# Processing.net
KiCad netlist of a schematic drawn in Altium Designer
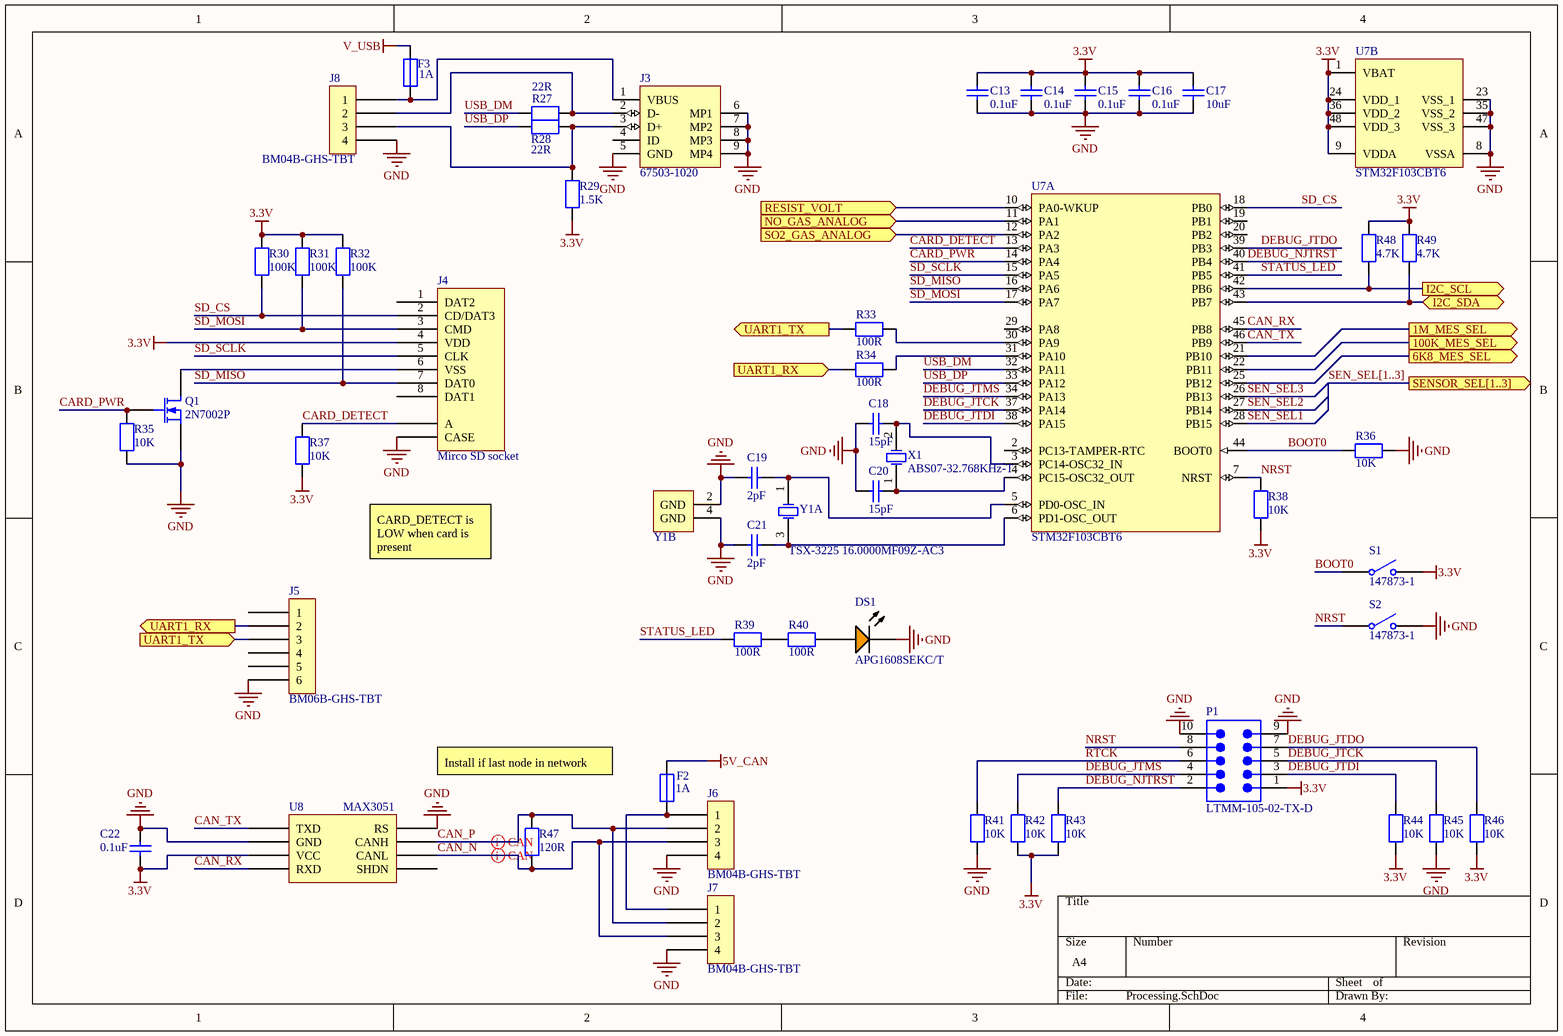
[diagram p0: Processing.SchDoc]

(export (version "E")
  (design (tool "Eeschema 10.0.6"))
  (components
    (comp (ref "C13")
      (value "0.1uF")
      (footprint "0603_CAP")
      (fields (field (name "Comment") "Capacitor"))
      (libsource (lib "Passive_comp") (part "Capacitor"))
    )
    (comp (ref "C14")
      (value "0.1uF")
      (footprint "0603_CAP")
      (fields (field (name "Comment") "Capacitor"))
      (libsource (lib "Passive_comp") (part "Capacitor"))
    )
    (comp (ref "C15")
      (value "0.1uF")
      (footprint "0603_CAP")
      (fields (field (name "Comment") "Capacitor"))
      (libsource (lib "Passive_comp") (part "Capacitor"))
    )
    (comp (ref "C16")
      (value "0.1uF")
      (footprint "0603_CAP")
      (fields (field (name "Comment") "Capacitor"))
      (libsource (lib "Passive_comp") (part "Capacitor"))
    )
    (comp (ref "C17")
      (value "10uF")
      (footprint "1206_CAP")
      (fields (field (name "Comment") "Capacitor"))
      (libsource (lib "Passive_comp") (part "Capacitor"))
    )
    (comp (ref "C18")
      (value "15pF")
      (footprint "0603_CAP")
      (fields (field (name "Comment") "Capacitor"))
      (libsource (lib "Passive_comp") (part "Capacitor"))
    )
    (comp (ref "C19")
      (value "2pF")
      (footprint "0603_CAP")
      (fields (field (name "Comment") "Capacitor"))
      (libsource (lib "Passive_comp") (part "Capacitor"))
    )
    (comp (ref "C20")
      (value "15pF")
      (footprint "0603_CAP")
      (fields (field (name "Comment") "Capacitor"))
      (libsource (lib "Passive_comp") (part "Capacitor"))
    )
    (comp (ref "C21")
      (value "2pF")
      (footprint "0603_CAP")
      (fields (field (name "Comment") "Capacitor"))
      (libsource (lib "Passive_comp") (part "Capacitor"))
    )
    (comp (ref "C22")
      (value "0.1uF")
      (footprint "0603_CAP")
      (fields (field (name "Comment") "Capacitor"))
      (libsource (lib "Passive_comp") (part "Capacitor"))
    )
    (comp (ref "DS1")
      (value "APG1608SEKC/T")
      (footprint "KING-LED0603-25-ORANGE_V")
      (description "LED, SMT, 0603(1608), 0.25mm Tthickness, Super Bright Orange")
      (libsource (lib "Altium Content Vault") (part "KING-LED_ORANGE_A1K2-2"))
    )
    (comp (ref "F2")
      (value "Fuse")
      (footprint "0603_RES")
      (fields (field (name "MAX_A") "1A"))
      (libsource (lib "Passive_comp") (part "Fuse"))
    )
    (comp (ref "F3")
      (value "Fuse")
      (footprint "0603_RES")
      (fields (field (name "MAX_A") "1A"))
      (libsource (lib "Passive_comp") (part "Fuse"))
    )
    (comp (ref "J3")
      (value "67503-1020")
      (footprint "MOLX-67503-1020_V")
      (description "USB, MINI, SMD, RA KME04-USBMU03A01")
      (fields (field (name "MANUFACTURER") "Molex"))
      (libsource (lib "Altium Content Vault") (part "MOLX-67503-1020"))
    )
    (comp (ref "J4")
      (value "Mirco SD socket")
      (footprint "HRS_DM3CS-SF")
      (libsource (lib "Misc_connectors") (part "Micro_SD"))
    )
    (comp (ref "J5")
      (value "BM06B-GHS-TBT")
      (footprint "BM06B-GHS-TBT")
      (description "JST GH top entry SMD connector")
      (libsource (lib "JST-GH") (part "BM06B-GHS-TBT"))
    )
    (comp (ref "J6")
      (value "BM04B-GHS-TBT")
      (footprint "BM04B-GHS-TBT")
      (description "JST GH top entry SMD connector")
      (libsource (lib "") (part "BM04B-GHS-TBT_1"))
    )
    (comp (ref "J7")
      (value "BM04B-GHS-TBT")
      (footprint "BM04B-GHS-TBT")
      (description "JST GH top entry SMD connector")
      (libsource (lib "") (part "BM04B-GHS-TBT_1"))
    )
    (comp (ref "J8")
      (value "BM04B-GHS-TBT")
      (footprint "BM04B-GHS-TBT")
      (description "JST GH top entry SMD connector")
      (libsource (lib "JST-GH") (part "BM04B-GHS-TBT"))
    )
    (comp (ref "P1")
      (value "LTMM-105-02-TX-D")
      (footprint "SMTC-LTMM-105-02-XX-D")
      (description "Shrouded Header & Stacker, Through-Hole, Vertical, -55 to 105 degC, 2 mm Pitch, 10-Pin, Male, RoHS")
      (fields (field (name "MANUFACTURER") "Samtec"))
      (libsource (lib "Altium Content Vault") (part "CMP-1028-00010-1"))
    )
    (comp (ref "Q1")
      (value "N-channel MOSFET")
      (footprint "SOT95P230X110-3M")
      (fields (field (name "PARTNUMBER") "2N7002P"))
      (libsource (lib "Active_comp") (part "MOSFET-N"))
    )
    (comp (ref "R27")
      (value "22R")
      (footprint "0603_RES")
      (fields (field (name "Comment") "Resitor"))
      (libsource (lib "") (part "Resitor_2"))
    )
    (comp (ref "R28")
      (value "22R")
      (footprint "0603_RES")
      (fields (field (name "Comment") "Resitor"))
      (libsource (lib "") (part "Resitor_2"))
    )
    (comp (ref "R29")
      (value "1.5K")
      (footprint "0603_RES")
      (fields (field (name "Comment") "Resitor"))
      (libsource (lib "") (part "Resitor_1"))
    )
    (comp (ref "R30")
      (value "100K")
      (footprint "0603_RES")
      (fields (field (name "Comment") "Resitor"))
      (libsource (lib "") (part "Resitor_1"))
    )
    (comp (ref "R31")
      (value "100K")
      (footprint "0603_RES")
      (fields (field (name "Comment") "Resitor"))
      (libsource (lib "") (part "Resitor_1"))
    )
    (comp (ref "R32")
      (value "100K")
      (footprint "0603_RES")
      (fields (field (name "Comment") "Resitor"))
      (libsource (lib "") (part "Resitor_1"))
    )
    (comp (ref "R33")
      (value "100R")
      (footprint "0603_RES")
      (fields (field (name "Comment") "Resitor"))
      (libsource (lib "") (part "Resitor_2"))
    )
    (comp (ref "R34")
      (value "100R")
      (footprint "0603_RES")
      (fields (field (name "Comment") "Resitor"))
      (libsource (lib "") (part "Resitor_2"))
    )
    (comp (ref "R35")
      (value "10K")
      (footprint "0603_RES")
      (fields (field (name "Comment") "Resitor"))
      (libsource (lib "Passive_comp") (part "Resitor"))
    )
    (comp (ref "R36")
      (value "10K")
      (footprint "0603_RES")
      (fields (field (name "Comment") "Resitor"))
      (libsource (lib "") (part "Resitor_3"))
    )
    (comp (ref "R37")
      (value "10K")
      (footprint "0603_RES")
      (fields (field (name "Comment") "Resitor"))
      (libsource (lib "Passive_comp") (part "Resitor"))
    )
    (comp (ref "R38")
      (value "10K")
      (footprint "0603_RES")
      (fields (field (name "Comment") "Resitor"))
      (libsource (lib "") (part "Resitor_1"))
    )
    (comp (ref "R39")
      (value "100R")
      (footprint "0603_RES")
      (fields (field (name "Comment") "Resitor"))
      (libsource (lib "") (part "Resitor_2"))
    )
    (comp (ref "R40")
      (value "100R")
      (footprint "0603_RES")
      (fields (field (name "Comment") "Resitor"))
      (libsource (lib "") (part "Resitor_2"))
    )
    (comp (ref "R41")
      (value "10K")
      (footprint "0603_RES")
      (fields (field (name "Comment") "Resitor"))
      (libsource (lib "") (part "Resitor_1"))
    )
    (comp (ref "R42")
      (value "10K")
      (footprint "0603_RES")
      (fields (field (name "Comment") "Resitor"))
      (libsource (lib "") (part "Resitor_1"))
    )
    (comp (ref "R43")
      (value "10K")
      (footprint "0603_RES")
      (fields (field (name "Comment") "Resitor"))
      (libsource (lib "Passive_comp") (part "Resitor"))
    )
    (comp (ref "R44")
      (value "10K")
      (footprint "0603_RES")
      (fields (field (name "Comment") "Resitor"))
      (libsource (lib "Passive_comp") (part "Resitor"))
    )
    (comp (ref "R45")
      (value "10K")
      (footprint "0603_RES")
      (fields (field (name "Comment") "Resitor"))
      (libsource (lib "Passive_comp") (part "Resitor"))
    )
    (comp (ref "R46")
      (value "10K")
      (footprint "0603_RES")
      (fields (field (name "Comment") "Resitor"))
      (libsource (lib "") (part "Resitor_1"))
    )
    (comp (ref "R47")
      (value "120R")
      (footprint "0603_RES")
      (fields (field (name "Comment") "Resitor"))
      (libsource (lib "") (part "Resitor_1"))
    )
    (comp (ref "R48")
      (value "4.7K")
      (footprint "0603_RES")
      (fields (field (name "Comment") "Resitor"))
      (libsource (lib "") (part "Resitor_1"))
    )
    (comp (ref "R49")
      (value "4.7K")
      (footprint "0603_RES")
      (fields (field (name "Comment") "Resitor"))
      (libsource (lib "") (part "Resitor_1"))
    )
    (comp (ref "S1")
      (value "147873-1")
      (footprint "147873-1")
      (description "Single-Pole, Single-Throw Switch")
      (fields (field (name "PUBLISHER") "Altium Limited"))
      (libsource (lib "Passive_comp") (part "SW-SPST"))
    )
    (comp (ref "S2")
      (value "147873-1")
      (footprint "147873-1")
      (description "Single-Pole, Single-Throw Switch")
      (fields (field (name "PUBLISHER") "Altium Limited"))
      (libsource (lib "Passive_comp") (part "SW-SPST"))
    )
    (comp (ref "U7")
      (value "STM32F103CBT6")
      (footprint "STM-LQFP48_L")
      (libsource (lib "Altium Content Vault") (part "MC-ARM-STM32F103X8_B-SQ48"))
    )
    (comp (ref "U8")
      (value "MAX3051")
      (footprint "SOIC127P600X175-8M")
      (libsource (lib "Active_comp") (part "MAX3051"))
    )
    (comp (ref "X1")
      (value "ABS07-32.768KHz-T")
      (footprint "ABRA-ABS07-2_V")
      (description "Crystal, 32.768 kHz, 12.5 pF, -40 to 85 degC, SMD Low Profile 3.2 x 1.5 x 0.9 mm, Tape and Reel")
      (fields (field (name "MANUFACTURER") "Abracon"))
      (libsource (lib "Altium Content Vault") (part "ABRA-ABS07-2"))
    )
    (comp (ref "Y1")
      (value "TSX-3225 16.0000MF09Z-AC3")
      (footprint "TSX-3225")
      (libsource (lib "Passive_comp") (part "TSX-3225 16.0000MF09Z-AC3"))
    )
  )
  (nets
    (net (code "1") (name "/1M_MES_SEL") (class "Default")
      (node (ref "U7") (pin "21") (pinfunction "PB10_21") (pintype "bidirectional"))
    )
    (net (code "2") (name "/6K8_MES_SEL") (class "Default")
      (node (ref "U7") (pin "25") (pinfunction "PB12_25") (pintype "bidirectional"))
    )
    (net (code "3") (name "/100K_MES_SEL") (class "Default")
      (node (ref "U7") (pin "22") (pinfunction "PB11_22") (pintype "bidirectional"))
    )
    (net (code "4") (name "/BOOT0") (class "Default")
      (node (ref "R36") (pin "2") (pinfunction "2_2") (pintype "passive"))
      (node (ref "S1") (pin "1") (pinfunction "COMMON_1") (pintype "passive"))
      (node (ref "U7") (pin "44") (pinfunction "BOOT0_44") (pintype "input"))
    )
    (net (code "5") (name "/CAN_N") (class "Default")
      (node (ref "J6") (pin "3") (pinfunction "3_3") (pintype "passive"))
      (node (ref "J7") (pin "3") (pinfunction "3_3") (pintype "passive"))
      (node (ref "R47") (pin "1") (pinfunction "1_1") (pintype "passive"))
      (node (ref "U8") (pin "6") (pinfunction "CANL_6") (pintype "passive"))
    )
    (net (code "6") (name "/CAN_P") (class "Default")
      (node (ref "J6") (pin "2") (pinfunction "2_2") (pintype "passive"))
      (node (ref "J7") (pin "2") (pinfunction "2_2") (pintype "passive"))
      (node (ref "R47") (pin "2") (pinfunction "2_2") (pintype "passive"))
      (node (ref "U8") (pin "7") (pinfunction "CANH_7") (pintype "passive"))
    )
    (net (code "7") (name "/CAN_RX") (class "Default")
      (node (ref "U7") (pin "45") (pinfunction "PB8_45") (pintype "bidirectional"))
      (node (ref "U8") (pin "4") (pinfunction "RXD_4") (pintype "passive"))
    )
    (net (code "8") (name "/CAN_TX") (class "Default")
      (node (ref "U7") (pin "46") (pinfunction "PB9_46") (pintype "bidirectional"))
      (node (ref "U8") (pin "1") (pinfunction "TXD_1") (pintype "passive"))
    )
    (net (code "9") (name "/CARD_DETECT") (class "Default")
      (node (ref "J4") (pin "A") (pinfunction "A_A") (pintype "passive"))
      (node (ref "R37") (pin "1") (pinfunction "1_1") (pintype "passive"))
      (node (ref "U7") (pin "13") (pinfunction "PA3_13") (pintype "bidirectional"))
    )
    (net (code "10") (name "/CARD_PWR") (class "Default")
      (node (ref "Q1") (pin "2") (pinfunction "G_2") (pintype "passive"))
      (node (ref "R35") (pin "1") (pinfunction "1_1") (pintype "passive"))
      (node (ref "U7") (pin "14") (pinfunction "PA4_14") (pintype "bidirectional"))
    )
    (net (code "11") (name "/DEBUG_JTCK") (class "Default")
      (node (ref "P1") (pin "5") (pinfunction "5_5") (pintype "passive"))
      (node (ref "R45") (pin "1") (pinfunction "1_1") (pintype "passive"))
      (node (ref "U7") (pin "37") (pinfunction "PA14_37") (pintype "bidirectional"))
    )
    (net (code "12") (name "/DEBUG_JTDI") (class "Default")
      (node (ref "P1") (pin "3") (pinfunction "3_3") (pintype "passive"))
      (node (ref "R44") (pin "1") (pinfunction "1_1") (pintype "passive"))
      (node (ref "U7") (pin "38") (pinfunction "PA15_38") (pintype "bidirectional"))
    )
    (net (code "13") (name "/DEBUG_JTDO") (class "Default")
      (node (ref "P1") (pin "7") (pinfunction "7_7") (pintype "passive"))
      (node (ref "R46") (pin "2") (pinfunction "2_2") (pintype "passive"))
      (node (ref "U7") (pin "39") (pinfunction "PB3_39") (pintype "bidirectional"))
    )
    (net (code "14") (name "/DEBUG_JTMS") (class "Default")
      (node (ref "P1") (pin "4") (pinfunction "4_4") (pintype "passive"))
      (node (ref "R42") (pin "2") (pinfunction "2_2") (pintype "passive"))
      (node (ref "U7") (pin "34") (pinfunction "PA13_34") (pintype "bidirectional"))
    )
    (net (code "15") (name "/DEBUG_NJTRST") (class "Default")
      (node (ref "P1") (pin "2") (pinfunction "2_2") (pintype "passive"))
      (node (ref "R43") (pin "1") (pinfunction "1_1") (pintype "passive"))
      (node (ref "U7") (pin "40") (pinfunction "PB4_40") (pintype "bidirectional"))
    )
    (net (code "16") (name "/I2C_SCL") (class "Default")
      (node (ref "R48") (pin "1") (pinfunction "1_1") (pintype "passive"))
      (node (ref "U7") (pin "42") (pinfunction "PB6_42") (pintype "bidirectional"))
    )
    (net (code "17") (name "/I2C_SDA") (class "Default")
      (node (ref "R49") (pin "1") (pinfunction "1_1") (pintype "passive"))
      (node (ref "U7") (pin "43") (pinfunction "PB7_43") (pintype "bidirectional"))
    )
    (net (code "18") (name "/NO_GAS_ANALOG") (class "Default")
      (node (ref "U7") (pin "11") (pinfunction "PA1_11") (pintype "bidirectional"))
    )
    (net (code "19") (name "/NRST") (class "Default")
      (node (ref "P1") (pin "8") (pinfunction "8_8") (pintype "passive"))
      (node (ref "R38") (pin "2") (pinfunction "2_2") (pintype "passive"))
      (node (ref "S2") (pin "1") (pinfunction "COMMON_1") (pintype "passive"))
      (node (ref "U7") (pin "7") (pinfunction "NRST_7") (pintype "bidirectional"))
    )
    (net (code "20") (name "/RESIST_VOLT") (class "Default")
      (node (ref "U7") (pin "10") (pinfunction "PA0-WKUP_10") (pintype "bidirectional"))
    )
    (net (code "21") (name "/RTCK") (class "Default")
      (node (ref "P1") (pin "6") (pinfunction "6_6") (pintype "passive"))
      (node (ref "R41") (pin "2") (pinfunction "2_2") (pintype "passive"))
    )
    (net (code "22") (name "/SD_CS") (class "Default")
      (node (ref "J4") (pin "2") (pinfunction "CD/DAT3_2") (pintype "passive"))
      (node (ref "R30") (pin "1") (pinfunction "1_1") (pintype "passive"))
      (node (ref "U7") (pin "18") (pinfunction "PB0_18") (pintype "bidirectional"))
    )
    (net (code "23") (name "/SD_MISO") (class "Default")
      (node (ref "J4") (pin "7") (pinfunction "DAT0_7") (pintype "passive"))
      (node (ref "R32") (pin "1") (pinfunction "1_1") (pintype "passive"))
      (node (ref "U7") (pin "16") (pinfunction "PA6_16") (pintype "bidirectional"))
    )
    (net (code "24") (name "/SD_MOSI") (class "Default")
      (node (ref "J4") (pin "3") (pinfunction "CMD_3") (pintype "passive"))
      (node (ref "R31") (pin "1") (pinfunction "1_1") (pintype "passive"))
      (node (ref "U7") (pin "17") (pinfunction "PA7_17") (pintype "bidirectional"))
    )
    (net (code "25") (name "/SD_SCLK") (class "Default")
      (node (ref "J4") (pin "5") (pinfunction "CLK_5") (pintype "passive"))
      (node (ref "U7") (pin "15") (pinfunction "PA5_15") (pintype "bidirectional"))
    )
    (net (code "26") (name "/SEN_SEL1") (class "Default")
      (node (ref "U7") (pin "28") (pinfunction "PB15_28") (pintype "bidirectional"))
    )
    (net (code "27") (name "/SEN_SEL2") (class "Default")
      (node (ref "U7") (pin "27") (pinfunction "PB14_27") (pintype "bidirectional"))
    )
    (net (code "28") (name "/SEN_SEL3") (class "Default")
      (node (ref "U7") (pin "26") (pinfunction "PB13_26") (pintype "bidirectional"))
    )
    (net (code "30") (name "/SO2_GAS_ANALOG") (class "Default")
      (node (ref "U7") (pin "12") (pinfunction "PA2_12") (pintype "bidirectional"))
    )
    (net (code "31") (name "/STATUS_LED") (class "Default")
      (node (ref "R39") (pin "1") (pinfunction "1_1") (pintype "passive"))
      (node (ref "U7") (pin "41") (pinfunction "PB5_41") (pintype "bidirectional"))
    )
    (net (code "32") (name "/UART1_RX") (class "Default")
      (node (ref "J5") (pin "2") (pinfunction "2_2") (pintype "passive"))
      (node (ref "R34") (pin "1") (pinfunction "1_1") (pintype "passive"))
    )
    (net (code "33") (name "/UART1_TX") (class "Default")
      (node (ref "J5") (pin "3") (pinfunction "3_3") (pintype "passive"))
      (node (ref "R33") (pin "1") (pinfunction "1_1") (pintype "passive"))
    )
    (net (code "34") (name "/USB_DM") (class "Default")
      (node (ref "R27") (pin "1") (pinfunction "1_1") (pintype "passive"))
      (node (ref "U7") (pin "32") (pinfunction "PA11_32") (pintype "bidirectional"))
    )
    (net (code "35") (name "/USB_DP") (class "Default")
      (node (ref "R28") (pin "1") (pinfunction "1_1") (pintype "passive"))
      (node (ref "U7") (pin "33") (pinfunction "PA12_33") (pintype "bidirectional"))
    )
    (net (code "36") (name "3.3V") (class "Default")
      (node (ref "C13") (pin "2") (pinfunction "2_2") (pintype "passive"))
      (node (ref "C14") (pin "2") (pinfunction "2_2") (pintype "passive"))
      (node (ref "C15") (pin "2") (pinfunction "2_2") (pintype "passive"))
      (node (ref "C16") (pin "2") (pinfunction "2_2") (pintype "passive"))
      (node (ref "C17") (pin "2") (pinfunction "2_2") (pintype "passive"))
      (node (ref "C22") (pin "1") (pinfunction "1_1") (pintype "passive"))
      (node (ref "J4") (pin "4") (pinfunction "VDD_4") (pintype "passive"))
      (node (ref "P1") (pin "1") (pinfunction "1_1") (pintype "passive"))
      (node (ref "R29") (pin "1") (pinfunction "1_1") (pintype "passive"))
      (node (ref "R30") (pin "2") (pinfunction "2_2") (pintype "passive"))
      (node (ref "R31") (pin "2") (pinfunction "2_2") (pintype "passive"))
      (node (ref "R32") (pin "2") (pinfunction "2_2") (pintype "passive"))
      (node (ref "R37") (pin "2") (pinfunction "2_2") (pintype "passive"))
      (node (ref "R38") (pin "1") (pinfunction "1_1") (pintype "passive"))
      (node (ref "R42") (pin "1") (pinfunction "1_1") (pintype "passive"))
      (node (ref "R43") (pin "2") (pinfunction "2_2") (pintype "passive"))
      (node (ref "R44") (pin "2") (pinfunction "2_2") (pintype "passive"))
      (node (ref "R46") (pin "1") (pinfunction "1_1") (pintype "passive"))
      (node (ref "R48") (pin "2") (pinfunction "2_2") (pintype "passive"))
      (node (ref "R49") (pin "2") (pinfunction "2_2") (pintype "passive"))
      (node (ref "S1") (pin "2") (pinfunction "NO_2") (pintype "passive"))
      (node (ref "U7") (pin "1") (pinfunction "VBAT_1") (pintype "power_in"))
      (node (ref "U7") (pin "24") (pinfunction "VDD_1_24") (pintype "power_in"))
      (node (ref "U7") (pin "36") (pinfunction "VDD_2_36") (pintype "power_in"))
      (node (ref "U7") (pin "48") (pinfunction "VDD_3_48") (pintype "power_in"))
      (node (ref "U7") (pin "9") (pinfunction "VDDA_9") (pintype "power_in"))
      (node (ref "U8") (pin "3") (pinfunction "VCC_3") (pintype "passive"))
    )
    (net (code "37") (name "5V_CAN") (class "Default")
      (node (ref "F2") (pin "2") (pinfunction "2_2") (pintype "passive"))
    )
    (net (code "38") (name "GND") (class "Default")
      (node (ref "C13") (pin "1") (pinfunction "1_1") (pintype "passive"))
      (node (ref "C14") (pin "1") (pinfunction "1_1") (pintype "passive"))
      (node (ref "C15") (pin "1") (pinfunction "1_1") (pintype "passive"))
      (node (ref "C16") (pin "1") (pinfunction "1_1") (pintype "passive"))
      (node (ref "C17") (pin "1") (pinfunction "1_1") (pintype "passive"))
      (node (ref "C18") (pin "1") (pinfunction "1_1") (pintype "passive"))
      (node (ref "C19") (pin "1") (pinfunction "1_1") (pintype "passive"))
      (node (ref "C20") (pin "1") (pinfunction "1_1") (pintype "passive"))
      (node (ref "C21") (pin "1") (pinfunction "1_1") (pintype "passive"))
      (node (ref "C22") (pin "2") (pinfunction "2_2") (pintype "passive"))
      (node (ref "DS1") (pin "2") (pinfunction "K_2") (pintype "passive"))
      (node (ref "J3") (pin "5") (pinfunction "GND_5") (pintype "power_in"))
      (node (ref "J3") (pin "6") (pinfunction "MP1_6") (pintype "passive"))
      (node (ref "J3") (pin "7") (pinfunction "MP2_7") (pintype "passive"))
      (node (ref "J3") (pin "8") (pinfunction "MP3_8") (pintype "passive"))
      (node (ref "J3") (pin "9") (pinfunction "MP4_9") (pintype "passive"))
      (node (ref "J4") (pin "0") (pinfunction "CASE_0") (pintype "passive"))
      (node (ref "J5") (pin "6") (pinfunction "6_6") (pintype "passive"))
      (node (ref "J6") (pin "4") (pinfunction "4_4") (pintype "passive"))
      (node (ref "J7") (pin "4") (pinfunction "4_4") (pintype "passive"))
      (node (ref "J8") (pin "4") (pinfunction "4_4") (pintype "passive"))
      (node (ref "P1") (pin "10") (pinfunction "10_10") (pintype "passive"))
      (node (ref "P1") (pin "9") (pinfunction "9_9") (pintype "passive"))
      (node (ref "Q1") (pin "3") (pinfunction "S_3") (pintype "passive"))
      (node (ref "R35") (pin "2") (pinfunction "2_2") (pintype "passive"))
      (node (ref "R36") (pin "1") (pinfunction "1_1") (pintype "passive"))
      (node (ref "R41") (pin "1") (pinfunction "1_1") (pintype "passive"))
      (node (ref "R45") (pin "2") (pinfunction "2_2") (pintype "passive"))
      (node (ref "S2") (pin "2") (pinfunction "NO_2") (pintype "passive"))
      (node (ref "U7") (pin "23") (pinfunction "VSS_1_23") (pintype "power_in"))
      (node (ref "U7") (pin "35") (pinfunction "VSS_2_35") (pintype "power_in"))
      (node (ref "U7") (pin "47") (pinfunction "VSS_3_47") (pintype "power_in"))
      (node (ref "U7") (pin "8") (pinfunction "VSSA_8") (pintype "power_in"))
      (node (ref "U8") (pin "2") (pinfunction "GND_2") (pintype "passive"))
      (node (ref "U8") (pin "8") (pinfunction "RS_8") (pintype "passive"))
      (node (ref "Y1") (pin "2") (pinfunction "GND_2") (pintype "power_in"))
      (node (ref "Y1") (pin "4") (pinfunction "GND_4") (pintype "power_in"))
    )
    (net (code "39") (name "Net-(DS1-A)") (class "Default")
      (node (ref "DS1") (pin "1") (pinfunction "A_1") (pintype "passive"))
      (node (ref "R40") (pin "2") (pinfunction "2_2") (pintype "passive"))
    )
    (net (code "40") (name "Net-(F2-Pad1)") (class "Default")
      (node (ref "F2") (pin "1") (pinfunction "1_1") (pintype "passive"))
      (node (ref "J6") (pin "1") (pinfunction "1_1") (pintype "passive"))
      (node (ref "J7") (pin "1") (pinfunction "1_1") (pintype "passive"))
    )
    (net (code "41") (name "Net-(J3-D+)") (class "Default")
      (node (ref "J3") (pin "3") (pinfunction "D+_3") (pintype "bidirectional"))
      (node (ref "J8") (pin "3") (pinfunction "3_3") (pintype "passive"))
      (node (ref "R28") (pin "2") (pinfunction "2_2") (pintype "passive"))
      (node (ref "R29") (pin "2") (pinfunction "2_2") (pintype "passive"))
    )
    (net (code "42") (name "Net-(J3-D-)") (class "Default")
      (node (ref "J3") (pin "2") (pinfunction "D-_2") (pintype "bidirectional"))
      (node (ref "J8") (pin "2") (pinfunction "2_2") (pintype "passive"))
      (node (ref "R27") (pin "2") (pinfunction "2_2") (pintype "passive"))
    )
    (net (code "43") (name "Net-(J3-VBUS)") (class "Default")
      (node (ref "F3") (pin "1") (pinfunction "1_1") (pintype "passive"))
      (node (ref "J3") (pin "1") (pinfunction "VBUS_1") (pintype "power_in"))
      (node (ref "J8") (pin "1") (pinfunction "1_1") (pintype "passive"))
    )
    (net (code "44") (name "Net-(J4-VSS)") (class "Default")
      (node (ref "J4") (pin "6") (pinfunction "VSS_6") (pintype "passive"))
      (node (ref "Q1") (pin "1") (pinfunction "D_1") (pintype "passive"))
    )
    (net (code "45") (name "Net-(R39-Pad2)") (class "Default")
      (node (ref "R39") (pin "2") (pinfunction "2_2") (pintype "passive"))
      (node (ref "R40") (pin "1") (pinfunction "1_1") (pintype "passive"))
    )
    (net (code "46") (name "Net-(U7A-PA9)") (class "Default")
      (node (ref "R33") (pin "2") (pinfunction "2_2") (pintype "passive"))
      (node (ref "U7") (pin "30") (pinfunction "PA9_30") (pintype "bidirectional"))
    )
    (net (code "47") (name "Net-(U7A-PA10)") (class "Default")
      (node (ref "R34") (pin "2") (pinfunction "2_2") (pintype "passive"))
      (node (ref "U7") (pin "31") (pinfunction "PA10_31") (pintype "bidirectional"))
    )
    (net (code "48") (name "Net-(U7A-PC14-OSC32_IN)") (class "Default")
      (node (ref "C18") (pin "2") (pinfunction "2_2") (pintype "passive"))
      (node (ref "U7") (pin "3") (pinfunction "PC14-OSC32_IN_3") (pintype "bidirectional"))
      (node (ref "X1") (pin "2") (pinfunction "X2_2") (pintype "passive"))
    )
    (net (code "49") (name "Net-(U7A-PC15-OSC32_OUT)") (class "Default")
      (node (ref "C20") (pin "2") (pinfunction "2_2") (pintype "passive"))
      (node (ref "U7") (pin "4") (pinfunction "PC15-OSC32_OUT_4") (pintype "bidirectional"))
      (node (ref "X1") (pin "1") (pinfunction "X1_1") (pintype "passive"))
    )
    (net (code "50") (name "Net-(U7A-PD0-OSC_IN)") (class "Default")
      (node (ref "C19") (pin "2") (pinfunction "2_2") (pintype "passive"))
      (node (ref "U7") (pin "5") (pinfunction "PD0-OSC_IN_5") (pintype "bidirectional"))
      (node (ref "Y1") (pin "1") (pinfunction "X1_1") (pintype "passive"))
    )
    (net (code "51") (name "Net-(U7A-PD1-OSC_OUT)") (class "Default")
      (node (ref "C21") (pin "2") (pinfunction "2_2") (pintype "passive"))
      (node (ref "U7") (pin "6") (pinfunction "PD1-OSC_OUT_6") (pintype "bidirectional"))
      (node (ref "Y1") (pin "3") (pinfunction "X2_3") (pintype "passive"))
    )
    (net (code "52") (name "V_USB") (class "Default")
      (node (ref "F3") (pin "2") (pinfunction "2_2") (pintype "passive"))
    )
    (net (code "53") (name "unconnected-(J3-ID-Pad4)") (class "Default")
      (node (ref "J3") (pin "4") (pinfunction "ID_4") (pintype "passive"))
    )
    (net (code "54") (name "unconnected-(J4-DAT1-Pad8)") (class "Default")
      (node (ref "J4") (pin "8") (pinfunction "DAT1_8") (pintype "passive"))
    )
    (net (code "55") (name "unconnected-(J4-DAT2-Pad1)") (class "Default")
      (node (ref "J4") (pin "1") (pinfunction "DAT2_1") (pintype "passive"))
    )
    (net (code "56") (name "unconnected-(J5-Pad1)") (class "Default")
      (node (ref "J5") (pin "1") (pinfunction "1_1") (pintype "passive"))
    )
    (net (code "57") (name "unconnected-(J5-Pad4)") (class "Default")
      (node (ref "J5") (pin "4") (pinfunction "4_4") (pintype "passive"))
    )
    (net (code "58") (name "unconnected-(J5-Pad5)") (class "Default")
      (node (ref "J5") (pin "5") (pinfunction "5_5") (pintype "passive"))
    )
    (net (code "59") (name "unconnected-(U7A-PA8-Pad29)") (class "Default")
      (node (ref "U7") (pin "29") (pinfunction "PA8_29") (pintype "bidirectional"))
    )
    (net (code "60") (name "unconnected-(U7A-PB1-Pad19)") (class "Default")
      (node (ref "U7") (pin "19") (pinfunction "PB1_19") (pintype "bidirectional"))
    )
    (net (code "61") (name "unconnected-(U7A-PB2-Pad20)") (class "Default")
      (node (ref "U7") (pin "20") (pinfunction "PB2_20") (pintype "bidirectional"))
    )
    (net (code "62") (name "unconnected-(U7A-PC13-TAMPER-RTC-Pad2)") (class "Default")
      (node (ref "U7") (pin "2") (pinfunction "PC13-TAMPER-RTC_2") (pintype "bidirectional"))
    )
    (net (code "63") (name "unconnected-(U8-SHDN-Pad5)") (class "Default")
      (node (ref "U8") (pin "5") (pinfunction "SHDN_5") (pintype "passive"))
    )
  )
)
